# Targets.net
KiCad netlist of a schematic drawn in Altium Designer
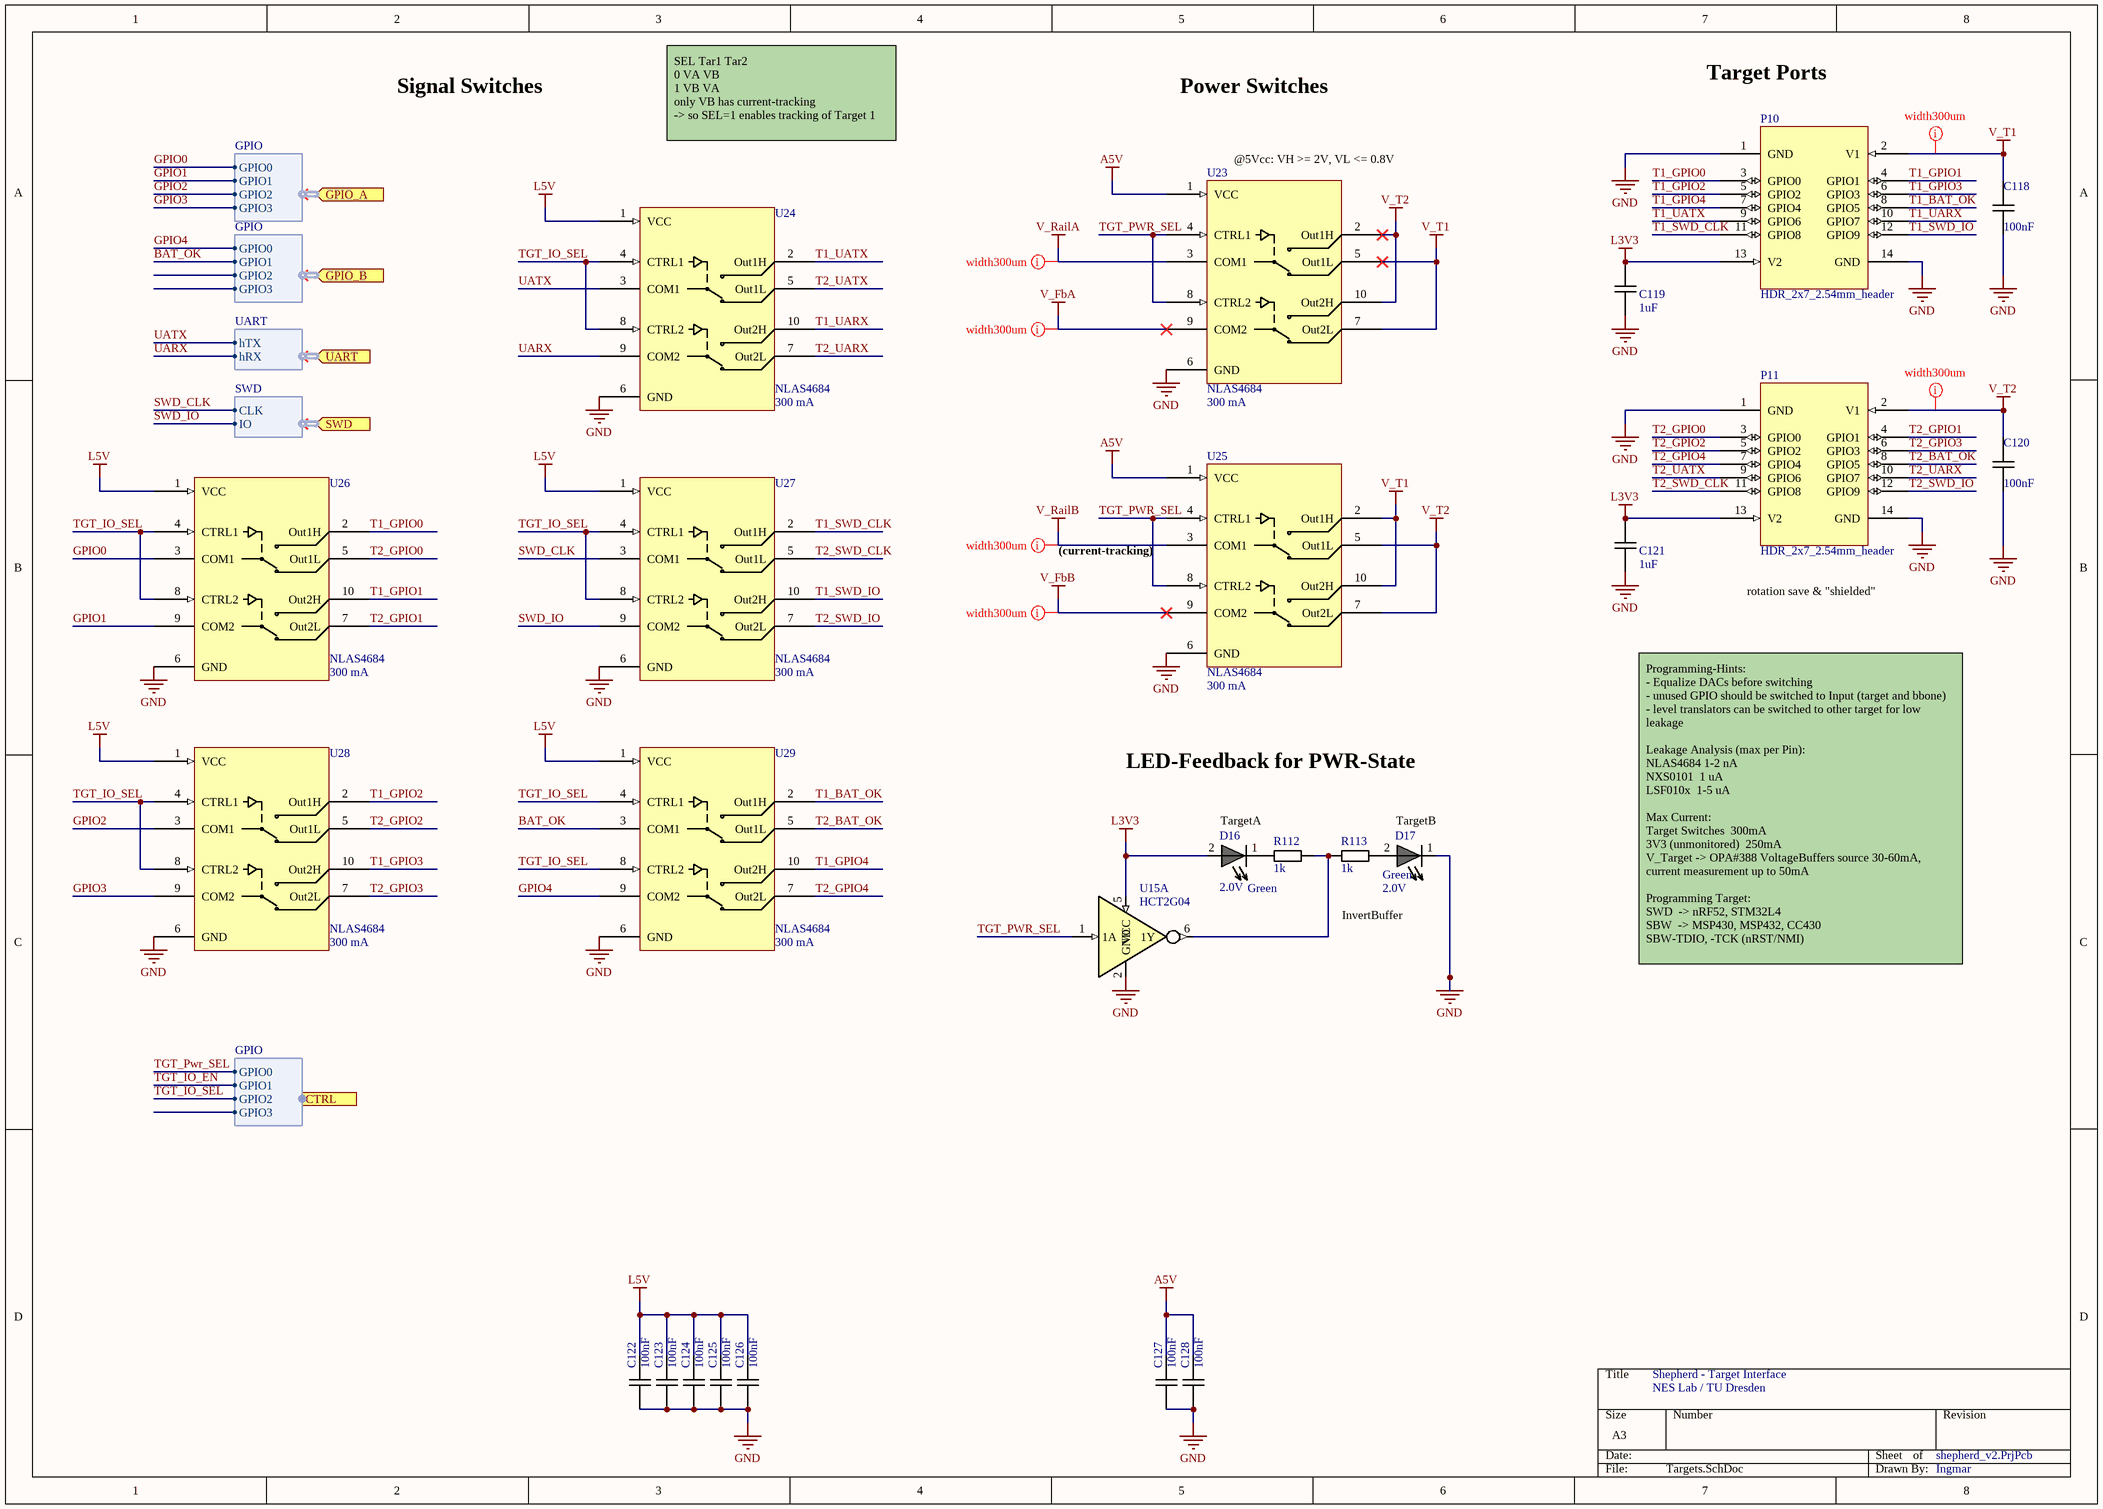
[diagram p0: Targets.SchDoc]

(export (version "E")
  (design (tool "Eeschema 10.0.6"))
  (components
    (comp (ref "C118")
      (value "100nF")
      (footprint "CAPC1005X06")
      (description "Capacitor")
      (fields (field (name "MANUFACTURER") "Taiyo Yuden") (field (name "TOLERANCE") "20%"))
      (libsource (lib "shepherd_parts") (part ".C_0402_100nF_16V"))
    )
    (comp (ref "C119")
      (value "1uF")
      (footprint "CAPC1005X06")
      (description "Capacitor")
      (fields (field (name "MANUFACTURER") "Murata") (field (name "TOLERANCE") "10%"))
      (libsource (lib "shepherd_parts") (part ".C_0402_1uF_25V"))
    )
    (comp (ref "C120")
      (value "100nF")
      (footprint "CAPC1005X06")
      (description "Capacitor")
      (fields (field (name "MANUFACTURER") "Taiyo Yuden") (field (name "TOLERANCE") "20%"))
      (libsource (lib "shepherd_parts") (part ".C_0402_100nF_16V"))
    )
    (comp (ref "C121")
      (value "1uF")
      (footprint "CAPC1005X06")
      (description "Capacitor")
      (fields (field (name "MANUFACTURER") "Murata") (field (name "TOLERANCE") "10%"))
      (libsource (lib "shepherd_parts") (part ".C_0402_1uF_25V"))
    )
    (comp (ref "C122")
      (value "100nF")
      (footprint "CAPC1005X06")
      (description "Capacitor")
      (fields (field (name "MANUFACTURER") "Taiyo Yuden") (field (name "TOLERANCE") "20%"))
      (libsource (lib "shepherd_parts") (part ".C_0402_100nF_16V"))
    )
    (comp (ref "C123")
      (value "100nF")
      (footprint "CAPC1005X06")
      (description "Capacitor")
      (fields (field (name "MANUFACTURER") "Taiyo Yuden") (field (name "TOLERANCE") "20%"))
      (libsource (lib "shepherd_parts") (part ".C_0402_100nF_16V"))
    )
    (comp (ref "C124")
      (value "100nF")
      (footprint "CAPC1005X06")
      (description "Capacitor")
      (fields (field (name "MANUFACTURER") "Taiyo Yuden") (field (name "TOLERANCE") "20%"))
      (libsource (lib "shepherd_parts") (part ".C_0402_100nF_16V"))
    )
    (comp (ref "C125")
      (value "100nF")
      (footprint "CAPC1005X06")
      (description "Capacitor")
      (fields (field (name "MANUFACTURER") "Taiyo Yuden") (field (name "TOLERANCE") "20%"))
      (libsource (lib "shepherd_parts") (part ".C_0402_100nF_16V"))
    )
    (comp (ref "C126")
      (value "100nF")
      (footprint "CAPC1005X06")
      (description "Capacitor")
      (fields (field (name "MANUFACTURER") "Taiyo Yuden") (field (name "TOLERANCE") "20%"))
      (libsource (lib "shepherd_parts") (part ".C_0402_100nF_16V"))
    )
    (comp (ref "C127")
      (value "100nF")
      (footprint "CAPC1005X06")
      (description "Capacitor")
      (fields (field (name "MANUFACTURER") "Taiyo Yuden") (field (name "TOLERANCE") "20%"))
      (libsource (lib "shepherd_parts") (part ".C_0402_100nF_16V"))
    )
    (comp (ref "C128")
      (value "100nF")
      (footprint "CAPC1005X06")
      (description "Capacitor")
      (fields (field (name "MANUFACTURER") "Taiyo Yuden") (field (name "TOLERANCE") "20%"))
      (libsource (lib "shepherd_parts") (part ".C_0402_100nF_16V"))
    )
    (comp (ref "D16")
      (value "Green")
      (footprint "DIOM1608X02N Green")
      (description "LED YellowGreen 575nm, 0603, 60mcd 2V@20mA")
      (fields
        (field (name "MANUFACTURER") "Wuerth")
        (field (name "V_MAX") "2.0V")
        (field (name "Comment") "D_LED_0603_Green")
      )
      (libsource (lib "shepherd_parts") (part ".D_LED_0603_Green"))
    )
    (comp (ref "D17")
      (value "Green")
      (footprint "DIOM1608X02N Green")
      (description "LED YellowGreen 575nm, 0603, 60mcd 2V@20mA")
      (fields
        (field (name "MANUFACTURER") "Wuerth")
        (field (name "V_MAX") "2.0V")
        (field (name "Comment") "D_LED_0603_Green")
      )
      (libsource (lib "shepherd_parts") (part ".D_LED_0603_Green"))
    )
    (comp (ref "P10")
      (value "HDR_2x7_2.54mm_header")
      (footprint "P_Pinheader_2x7_R2.54mm_target")
      (description "Gold, Straight")
      (fields (field (name "MANUFACTURER") "Amphenol FCI"))
      (libsource (lib "shepherd_parts") (part ".P_HDR_2x7_2.54mm_male"))
    )
    (comp (ref "P11")
      (value "HDR_2x7_2.54mm_header")
      (footprint "P_Pinheader_2x7_R2.54mm_male")
      (description "Gold, Straight")
      (fields (field (name "MANUFACTURER") "Amphenol FCI"))
      (libsource (lib "shepherd_parts") (part ".P_HDR_2x7_2.54mm_male"))
    )
    (comp (ref "R112")
      (value "1k")
      (footprint "RESC1005X04")
      (description "Resistor")
      (fields (field (name "MANUFACTURER") "Panasonic") (field (name "TOLERANCE") "5%"))
      (libsource (lib "shepherd_parts") (part ".R_0402_1k"))
    )
    (comp (ref "R113")
      (value "1k")
      (footprint "RESC1005X04")
      (description "Resistor")
      (fields (field (name "MANUFACTURER") "Panasonic") (field (name "TOLERANCE") "5%"))
      (libsource (lib "shepherd_parts") (part ".R_0402_1k"))
    )
    (comp (ref "U15")
      (value "HCT2G04")
      (footprint "SOT65P210X110-6N")
      (description "Inverter Dual, Buffered, I_out +- 25mA max,")
      (fields (field (name "MANUFACTURER") "Nexperia"))
      (libsource (lib "shepherd_parts") (part "HCT2G04"))
    )
    (comp (ref "U23")
      (value "NLAS4684")
      (footprint "PSON50P300X100_HS-11N")
      (fields (field (name "MANUFACTURER") "ON Semi") (field (name "I_MAX") "300 mA"))
      (libsource (lib "shepherd_parts") (part "NLAS4684-MN"))
    )
    (comp (ref "U24")
      (value "NLAS4684")
      (footprint "PSON50P300X100_HS-11N")
      (fields (field (name "MANUFACTURER") "ON Semi") (field (name "I_MAX") "300 mA"))
      (libsource (lib "shepherd_parts") (part "NLAS4684-MN"))
    )
    (comp (ref "U25")
      (value "NLAS4684")
      (footprint "PSON50P300X100_HS-11N")
      (fields (field (name "MANUFACTURER") "ON Semi") (field (name "I_MAX") "300 mA"))
      (libsource (lib "shepherd_parts") (part "NLAS4684-MN"))
    )
    (comp (ref "U26")
      (value "NLAS4684")
      (footprint "PSON50P300X100_HS-11N")
      (fields (field (name "MANUFACTURER") "ON Semi") (field (name "I_MAX") "300 mA"))
      (libsource (lib "shepherd_parts") (part "NLAS4684-MN"))
    )
    (comp (ref "U27")
      (value "NLAS4684")
      (footprint "PSON50P300X100_HS-11N")
      (fields (field (name "MANUFACTURER") "ON Semi") (field (name "I_MAX") "300 mA"))
      (libsource (lib "shepherd_parts") (part "NLAS4684-MN"))
    )
    (comp (ref "U28")
      (value "NLAS4684")
      (footprint "PSON50P300X100_HS-11N")
      (fields (field (name "MANUFACTURER") "ON Semi") (field (name "I_MAX") "300 mA"))
      (libsource (lib "shepherd_parts") (part "NLAS4684-MN"))
    )
    (comp (ref "U29")
      (value "NLAS4684")
      (footprint "PSON50P300X100_HS-11N")
      (fields (field (name "MANUFACTURER") "ON Semi") (field (name "I_MAX") "300 mA"))
      (libsource (lib "shepherd_parts") (part "NLAS4684-MN"))
    )
  )
  (nets
    (net (code "4") (name "/BAT_OK") (class "Default")
      (node (ref "U29") (pin "3") (pinfunction "COM1_3") (pintype "passive"))
    )
    (net (code "5") (name "/GPIO0") (class "Default")
      (node (ref "U26") (pin "3") (pinfunction "COM1_3") (pintype "passive"))
    )
    (net (code "6") (name "/GPIO1") (class "Default")
      (node (ref "U26") (pin "9") (pinfunction "COM2_9") (pintype "passive"))
    )
    (net (code "7") (name "/GPIO2") (class "Default")
      (node (ref "U28") (pin "3") (pinfunction "COM1_3") (pintype "passive"))
    )
    (net (code "8") (name "/GPIO3") (class "Default")
      (node (ref "U28") (pin "9") (pinfunction "COM2_9") (pintype "passive"))
    )
    (net (code "9") (name "/GPIO4") (class "Default")
      (node (ref "U29") (pin "9") (pinfunction "COM2_9") (pintype "passive"))
    )
    (net (code "10") (name "/SWD_CLK") (class "Default")
      (node (ref "U27") (pin "3") (pinfunction "COM1_3") (pintype "passive"))
    )
    (net (code "11") (name "/SWD_IO") (class "Default")
      (node (ref "U27") (pin "9") (pinfunction "COM2_9") (pintype "passive"))
    )
    (net (code "12") (name "/T1_BAT_OK") (class "Default")
      (node (ref "P10") (pin "8") (pinfunction "GPIO5_8") (pintype "bidirectional"))
      (node (ref "U29") (pin "2") (pinfunction "Out1H_2") (pintype "passive"))
    )
    (net (code "13") (name "/T1_GPIO0") (class "Default")
      (node (ref "P10") (pin "3") (pinfunction "GPIO0_3") (pintype "bidirectional"))
      (node (ref "U26") (pin "2") (pinfunction "Out1H_2") (pintype "passive"))
    )
    (net (code "14") (name "/T1_GPIO1") (class "Default")
      (node (ref "P10") (pin "4") (pinfunction "GPIO1_4") (pintype "bidirectional"))
      (node (ref "U26") (pin "10") (pinfunction "Out2H_10") (pintype "passive"))
    )
    (net (code "15") (name "/T1_GPIO2") (class "Default")
      (node (ref "P10") (pin "5") (pinfunction "GPIO2_5") (pintype "bidirectional"))
      (node (ref "U28") (pin "2") (pinfunction "Out1H_2") (pintype "passive"))
    )
    (net (code "16") (name "/T1_GPIO3") (class "Default")
      (node (ref "P10") (pin "6") (pinfunction "GPIO3_6") (pintype "bidirectional"))
      (node (ref "U28") (pin "10") (pinfunction "Out2H_10") (pintype "passive"))
    )
    (net (code "17") (name "/T1_GPIO4") (class "Default")
      (node (ref "P10") (pin "7") (pinfunction "GPIO4_7") (pintype "bidirectional"))
      (node (ref "U29") (pin "10") (pinfunction "Out2H_10") (pintype "passive"))
    )
    (net (code "18") (name "/T1_SWD_CLK") (class "Default")
      (node (ref "P10") (pin "11") (pinfunction "GPIO8_11") (pintype "bidirectional"))
      (node (ref "U27") (pin "2") (pinfunction "Out1H_2") (pintype "passive"))
    )
    (net (code "19") (name "/T1_SWD_IO") (class "Default")
      (node (ref "P10") (pin "12") (pinfunction "GPIO9_12") (pintype "bidirectional"))
      (node (ref "U27") (pin "10") (pinfunction "Out2H_10") (pintype "passive"))
    )
    (net (code "20") (name "/T1_UARX") (class "Default")
      (node (ref "P10") (pin "10") (pinfunction "GPIO7_10") (pintype "bidirectional"))
      (node (ref "U24") (pin "10") (pinfunction "Out2H_10") (pintype "passive"))
    )
    (net (code "21") (name "/T1_UATX") (class "Default")
      (node (ref "P10") (pin "9") (pinfunction "GPIO6_9") (pintype "bidirectional"))
      (node (ref "U24") (pin "2") (pinfunction "Out1H_2") (pintype "passive"))
    )
    (net (code "22") (name "/T2_BAT_OK") (class "Default")
      (node (ref "P11") (pin "8") (pinfunction "GPIO5_8") (pintype "bidirectional"))
      (node (ref "U29") (pin "5") (pinfunction "Out1L_5") (pintype "passive"))
    )
    (net (code "23") (name "/T2_GPIO0") (class "Default")
      (node (ref "P11") (pin "3") (pinfunction "GPIO0_3") (pintype "bidirectional"))
      (node (ref "U26") (pin "5") (pinfunction "Out1L_5") (pintype "passive"))
    )
    (net (code "24") (name "/T2_GPIO1") (class "Default")
      (node (ref "P11") (pin "4") (pinfunction "GPIO1_4") (pintype "bidirectional"))
      (node (ref "U26") (pin "7") (pinfunction "Out2L_7") (pintype "passive"))
    )
    (net (code "25") (name "/T2_GPIO2") (class "Default")
      (node (ref "P11") (pin "5") (pinfunction "GPIO2_5") (pintype "bidirectional"))
      (node (ref "U28") (pin "5") (pinfunction "Out1L_5") (pintype "passive"))
    )
    (net (code "26") (name "/T2_GPIO3") (class "Default")
      (node (ref "P11") (pin "6") (pinfunction "GPIO3_6") (pintype "bidirectional"))
      (node (ref "U28") (pin "7") (pinfunction "Out2L_7") (pintype "passive"))
    )
    (net (code "27") (name "/T2_GPIO4") (class "Default")
      (node (ref "P11") (pin "7") (pinfunction "GPIO4_7") (pintype "bidirectional"))
      (node (ref "U29") (pin "7") (pinfunction "Out2L_7") (pintype "passive"))
    )
    (net (code "28") (name "/T2_SWD_CLK") (class "Default")
      (node (ref "P11") (pin "11") (pinfunction "GPIO8_11") (pintype "bidirectional"))
      (node (ref "U27") (pin "5") (pinfunction "Out1L_5") (pintype "passive"))
    )
    (net (code "29") (name "/T2_SWD_IO") (class "Default")
      (node (ref "P11") (pin "12") (pinfunction "GPIO9_12") (pintype "bidirectional"))
      (node (ref "U27") (pin "7") (pinfunction "Out2L_7") (pintype "passive"))
    )
    (net (code "30") (name "/T2_UARX") (class "Default")
      (node (ref "P11") (pin "10") (pinfunction "GPIO7_10") (pintype "bidirectional"))
      (node (ref "U24") (pin "7") (pinfunction "Out2L_7") (pintype "passive"))
    )
    (net (code "31") (name "/T2_UATX") (class "Default")
      (node (ref "P11") (pin "9") (pinfunction "GPIO6_9") (pintype "bidirectional"))
      (node (ref "U24") (pin "5") (pinfunction "Out1L_5") (pintype "passive"))
    )
    (net (code "33") (name "/TGT_IO_SEL") (class "Default")
      (node (ref "U24") (pin "4") (pinfunction "CTRL1_4") (pintype "input"))
      (node (ref "U24") (pin "8") (pinfunction "CTRL2_8") (pintype "input"))
      (node (ref "U26") (pin "4") (pinfunction "CTRL1_4") (pintype "input"))
      (node (ref "U26") (pin "8") (pinfunction "CTRL2_8") (pintype "input"))
      (node (ref "U27") (pin "4") (pinfunction "CTRL1_4") (pintype "input"))
      (node (ref "U27") (pin "8") (pinfunction "CTRL2_8") (pintype "input"))
      (node (ref "U28") (pin "4") (pinfunction "CTRL1_4") (pintype "input"))
      (node (ref "U28") (pin "8") (pinfunction "CTRL2_8") (pintype "input"))
      (node (ref "U29") (pin "4") (pinfunction "CTRL1_4") (pintype "input"))
      (node (ref "U29") (pin "8") (pinfunction "CTRL2_8") (pintype "input"))
    )
    (net (code "34") (name "/TGT_PWR_SEL") (class "Default")
      (node (ref "U15") (pin "1") (pinfunction "1A_1") (pintype "input"))
      (node (ref "U23") (pin "4") (pinfunction "CTRL1_4") (pintype "input"))
      (node (ref "U23") (pin "8") (pinfunction "CTRL2_8") (pintype "input"))
      (node (ref "U25") (pin "4") (pinfunction "CTRL1_4") (pintype "input"))
      (node (ref "U25") (pin "8") (pinfunction "CTRL2_8") (pintype "input"))
    )
    (net (code "36") (name "/UARX") (class "Default")
      (node (ref "U24") (pin "9") (pinfunction "COM2_9") (pintype "passive"))
    )
    (net (code "37") (name "/UATX") (class "Default")
      (node (ref "U24") (pin "3") (pinfunction "COM1_3") (pintype "passive"))
    )
    (net (code "41") (name "A5V") (class "Default")
      (node (ref "C127") (pin "2") (pinfunction "2_2") (pintype "passive"))
      (node (ref "C128") (pin "2") (pinfunction "2_2") (pintype "passive"))
      (node (ref "U23") (pin "1") (pinfunction "VCC_1") (pintype "input"))
      (node (ref "U25") (pin "1") (pinfunction "VCC_1") (pintype "input"))
    )
    (net (code "42") (name "GND") (class "Default")
      (node (ref "C118") (pin "1") (pinfunction "1_1") (pintype "passive"))
      (node (ref "C119") (pin "1") (pinfunction "1_1") (pintype "passive"))
      (node (ref "C120") (pin "1") (pinfunction "1_1") (pintype "passive"))
      (node (ref "C121") (pin "1") (pinfunction "1_1") (pintype "passive"))
      (node (ref "C122") (pin "1") (pinfunction "1_1") (pintype "passive"))
      (node (ref "C123") (pin "1") (pinfunction "1_1") (pintype "passive"))
      (node (ref "C124") (pin "1") (pinfunction "1_1") (pintype "passive"))
      (node (ref "C125") (pin "1") (pinfunction "1_1") (pintype "passive"))
      (node (ref "C126") (pin "1") (pinfunction "1_1") (pintype "passive"))
      (node (ref "C127") (pin "1") (pinfunction "1_1") (pintype "passive"))
      (node (ref "C128") (pin "1") (pinfunction "1_1") (pintype "passive"))
      (node (ref "D17") (pin "1") (pinfunction "1_1") (pintype "passive"))
      (node (ref "P10") (pin "1") (pinfunction "GND_1") (pintype "power_in"))
      (node (ref "P10") (pin "14") (pinfunction "GND_14") (pintype "power_in"))
      (node (ref "P11") (pin "1") (pinfunction "GND_1") (pintype "power_in"))
      (node (ref "P11") (pin "14") (pinfunction "GND_14") (pintype "power_in"))
      (node (ref "U15") (pin "2") (pinfunction "GND_2") (pintype "power_in"))
      (node (ref "U23") (pin "6") (pinfunction "GND_6") (pintype "power_in"))
      (node (ref "U24") (pin "6") (pinfunction "GND_6") (pintype "power_in"))
      (node (ref "U25") (pin "6") (pinfunction "GND_6") (pintype "power_in"))
      (node (ref "U26") (pin "6") (pinfunction "GND_6") (pintype "power_in"))
      (node (ref "U27") (pin "6") (pinfunction "GND_6") (pintype "power_in"))
      (node (ref "U28") (pin "6") (pinfunction "GND_6") (pintype "power_in"))
      (node (ref "U29") (pin "6") (pinfunction "GND_6") (pintype "power_in"))
    )
    (net (code "43") (name "L3V3") (class "Default")
      (node (ref "C119") (pin "2") (pinfunction "2_2") (pintype "passive"))
      (node (ref "C121") (pin "2") (pinfunction "2_2") (pintype "passive"))
      (node (ref "D16") (pin "2") (pinfunction "2_2") (pintype "passive"))
      (node (ref "P10") (pin "13") (pinfunction "V2_13") (pintype "input"))
      (node (ref "P11") (pin "13") (pinfunction "V2_13") (pintype "input"))
      (node (ref "U15") (pin "5") (pinfunction "VCC_5") (pintype "input"))
    )
    (net (code "44") (name "L5V") (class "Default")
      (node (ref "C122") (pin "2") (pinfunction "2_2") (pintype "passive"))
      (node (ref "C123") (pin "2") (pinfunction "2_2") (pintype "passive"))
      (node (ref "C124") (pin "2") (pinfunction "2_2") (pintype "passive"))
      (node (ref "C125") (pin "2") (pinfunction "2_2") (pintype "passive"))
      (node (ref "C126") (pin "2") (pinfunction "2_2") (pintype "passive"))
      (node (ref "U24") (pin "1") (pinfunction "VCC_1") (pintype "input"))
      (node (ref "U26") (pin "1") (pinfunction "VCC_1") (pintype "input"))
      (node (ref "U27") (pin "1") (pinfunction "VCC_1") (pintype "input"))
      (node (ref "U28") (pin "1") (pinfunction "VCC_1") (pintype "input"))
      (node (ref "U29") (pin "1") (pinfunction "VCC_1") (pintype "input"))
    )
    (net (code "45") (name "Net-(D16-Pad1)") (class "Default")
      (node (ref "D16") (pin "1") (pinfunction "1_1") (pintype "passive"))
      (node (ref "R112") (pin "1") (pinfunction "1_1") (pintype "passive"))
    )
    (net (code "46") (name "Net-(D17-Pad2)") (class "Default")
      (node (ref "D17") (pin "2") (pinfunction "2_2") (pintype "passive"))
      (node (ref "R113") (pin "1") (pinfunction "1_1") (pintype "passive"))
    )
    (net (code "47") (name "Net-(U15A-1Y)") (class "Default")
      (node (ref "R112") (pin "2") (pinfunction "2_2") (pintype "passive"))
      (node (ref "R113") (pin "2") (pinfunction "2_2") (pintype "passive"))
      (node (ref "U15") (pin "6") (pinfunction "1Y_6") (pintype "output"))
    )
    (net (code "48") (name "V_FbA") (class "Default")
      (node (ref "U23") (pin "9") (pinfunction "COM2_9") (pintype "passive"))
    )
    (net (code "49") (name "V_FbB") (class "Default")
      (node (ref "U25") (pin "9") (pinfunction "COM2_9") (pintype "passive"))
    )
    (net (code "50") (name "V_RailA") (class "Default")
      (node (ref "U23") (pin "3") (pinfunction "COM1_3") (pintype "passive"))
    )
    (net (code "51") (name "V_RailB") (class "Default")
      (node (ref "U25") (pin "3") (pinfunction "COM1_3") (pintype "passive"))
    )
    (net (code "52") (name "V_T1") (class "Default")
      (node (ref "C118") (pin "2") (pinfunction "2_2") (pintype "passive"))
      (node (ref "P10") (pin "2") (pinfunction "V1_2") (pintype "input"))
      (node (ref "U23") (pin "5") (pinfunction "Out1L_5") (pintype "passive"))
      (node (ref "U23") (pin "7") (pinfunction "Out2L_7") (pintype "passive"))
      (node (ref "U25") (pin "10") (pinfunction "Out2H_10") (pintype "passive"))
      (node (ref "U25") (pin "2") (pinfunction "Out1H_2") (pintype "passive"))
    )
    (net (code "53") (name "V_T2") (class "Default")
      (node (ref "C120") (pin "2") (pinfunction "2_2") (pintype "passive"))
      (node (ref "P11") (pin "2") (pinfunction "V1_2") (pintype "input"))
      (node (ref "U23") (pin "10") (pinfunction "Out2H_10") (pintype "passive"))
      (node (ref "U23") (pin "2") (pinfunction "Out1H_2") (pintype "passive"))
      (node (ref "U25") (pin "5") (pinfunction "Out1L_5") (pintype "passive"))
      (node (ref "U25") (pin "7") (pinfunction "Out2L_7") (pintype "passive"))
    )
  )
)
